# 0001.net
KiCad netlist of a schematic drawn in Altium Designer
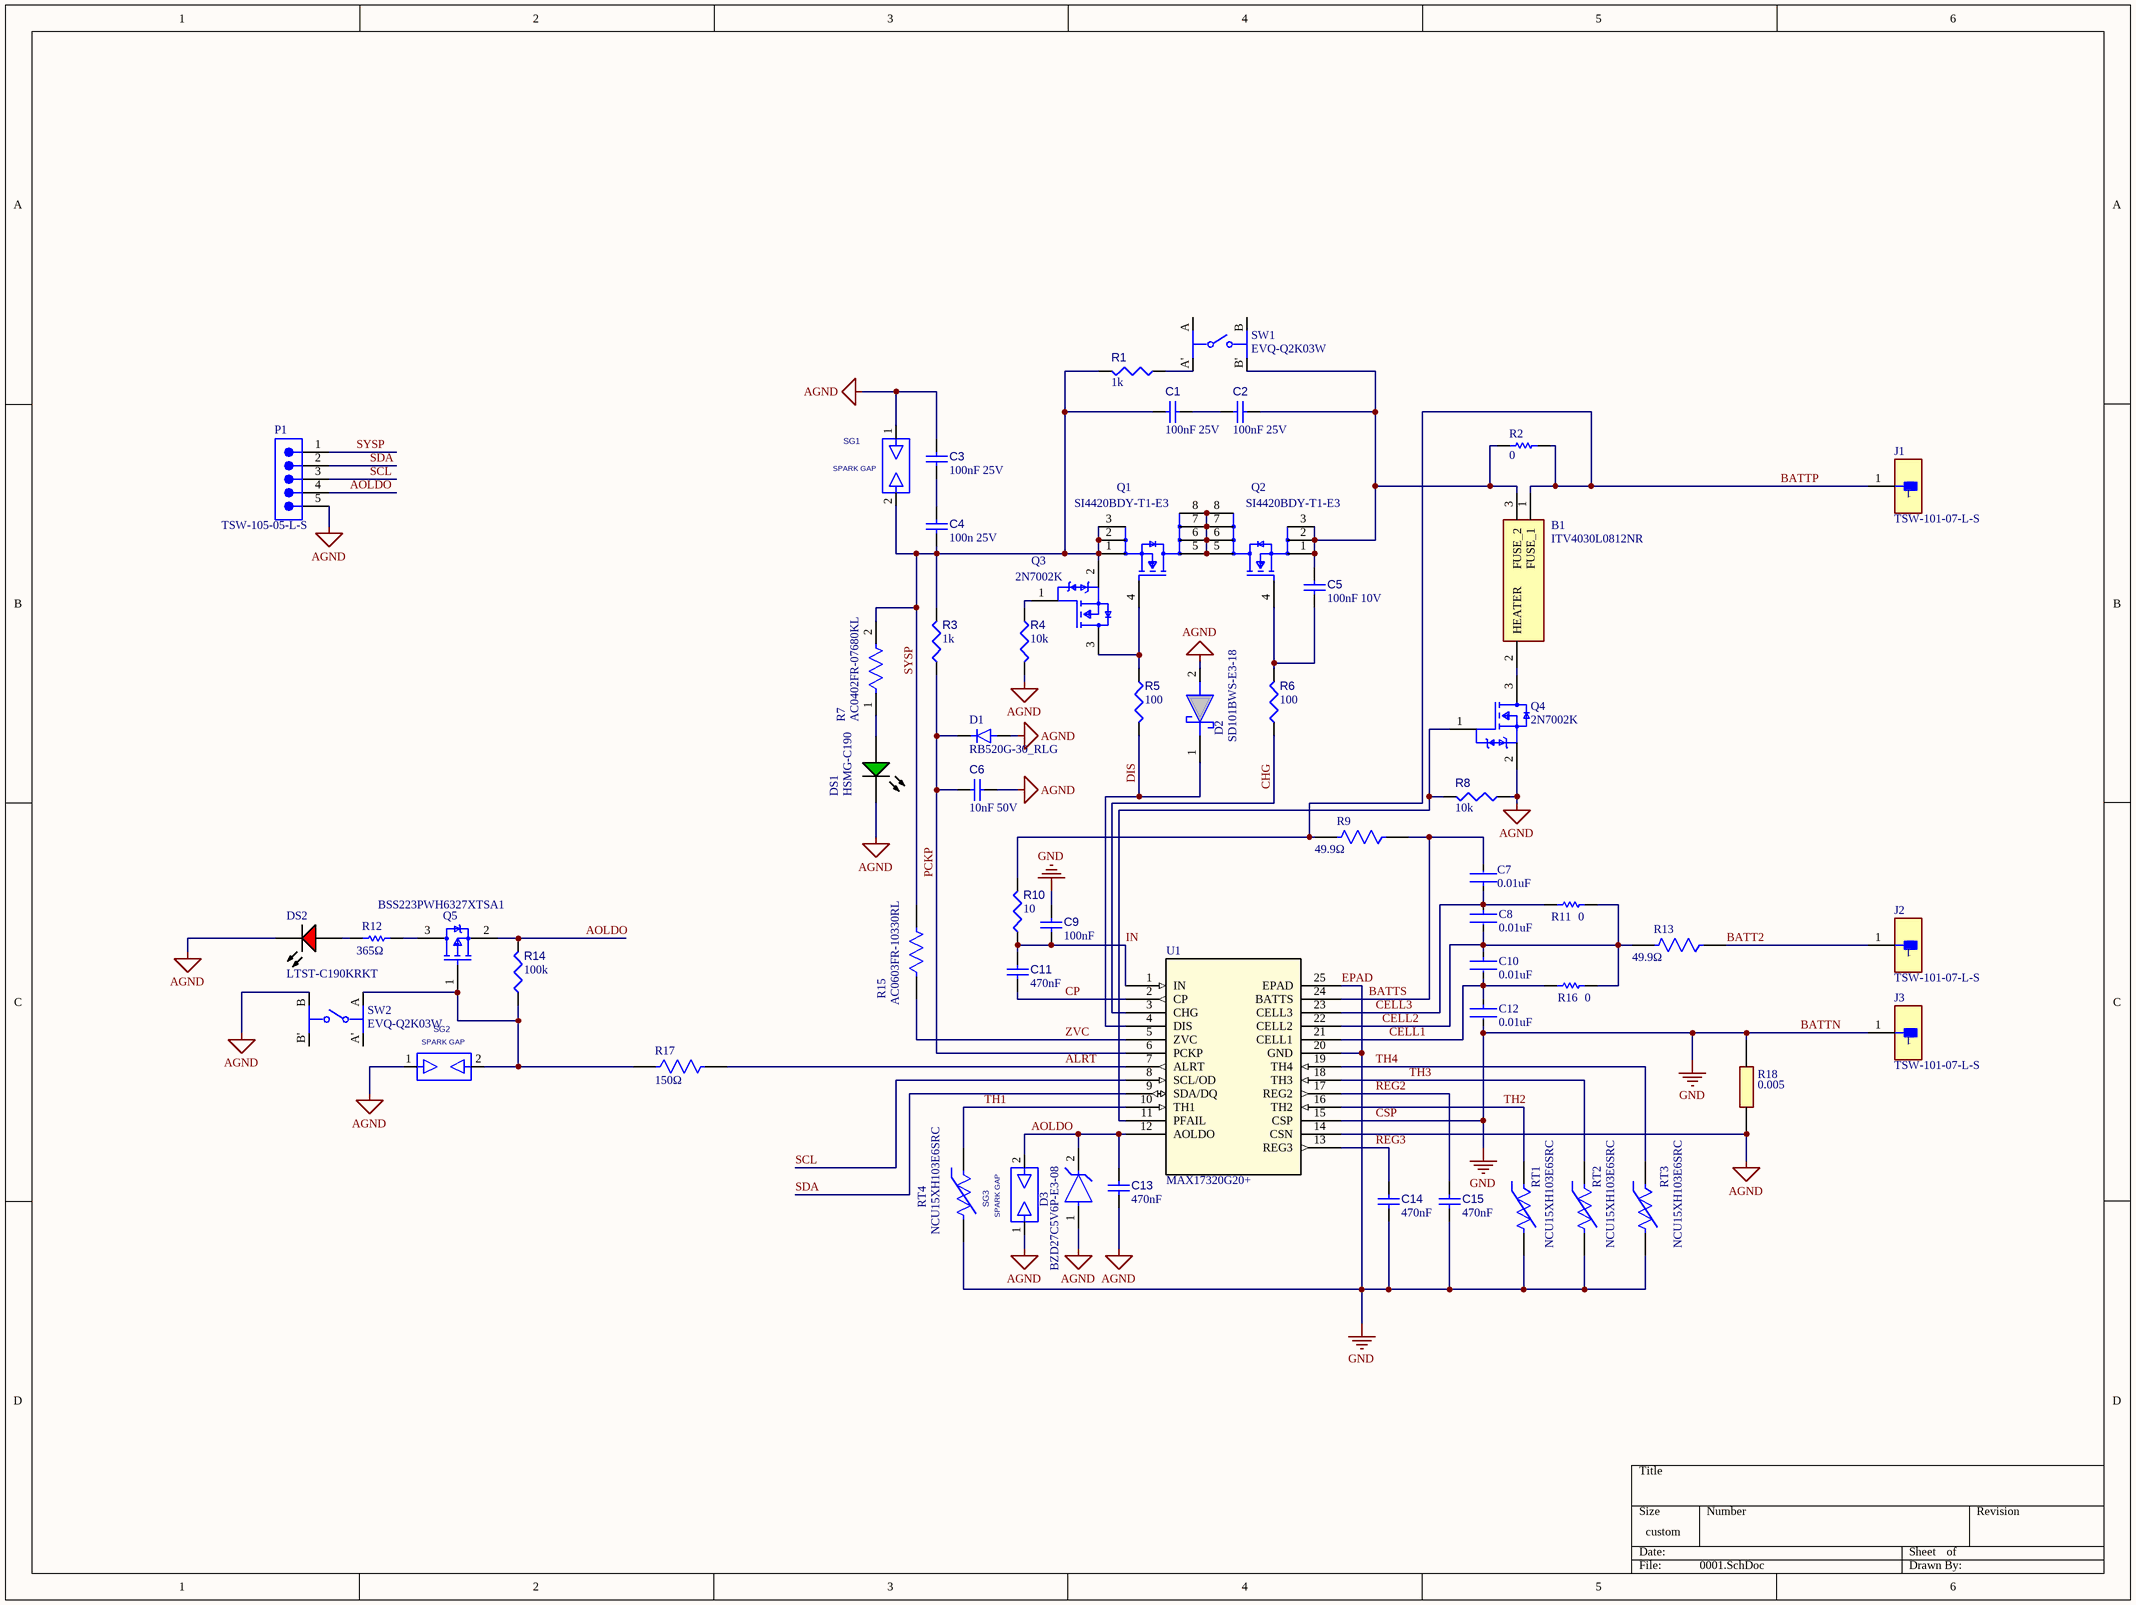
[diagram p0: 0001.SchDoc]

(export (version "E")
  (design (tool "Eeschema 10.0.6"))
  (components
    (comp (ref "B1")
      (value "ITV4030L0812NR")
      (footprint "ITV4030L0812NR")
      (description "Battery Management ITV 4.0*3.0MM 8V 12A")
      (fields (field (name "MOUSER PART NUMBER") "650-ITV4030L0812NR"))
      (libsource (lib "Pascal Doering") (part "ITV4030L0812NR"))
    )
    (comp (ref "C1")
      (value "100nF 25V")
      (footprint "CAPC0402(1005)60_L")
      (description "Chip Capacitor, 100nF +/-20%, 25V, 0402, Thickness 0.6 mm")
      (fields (field (name "TOLERANCE") "10%") (field (name "Comment") "Capacitor 100nF +/-20% 25V 0402"))
      (libsource (lib "Pascal Doering") (part "CAP-NP-2"))
    )
    (comp (ref "C2")
      (value "100nF 25V")
      (footprint "CAPC0402(1005)60_L")
      (description "Chip Capacitor, 100nF +/-20%, 25V, 0402, Thickness 0.6 mm")
      (fields (field (name "TOLERANCE") "10%") (field (name "Comment") "Capacitor 100nF +/-20% 25V 0402"))
      (libsource (lib "Pascal Doering") (part "CAP-NP-2"))
    )
    (comp (ref "C3")
      (value "100nF 25V")
      (footprint "CAPC0402(1005)60_L")
      (description "Chip Capacitor, 100nF +/-20%, 25V, 0402, Thickness 0.6 mm")
      (fields (field (name "TOLERANCE") "10%") (field (name "Comment") "Capacitor 100nF +/-20% 25V 0402"))
      (libsource (lib "Pascal Doering") (part "CAP-NP-2"))
    )
    (comp (ref "C4")
      (value "100n 25V")
      (footprint "CAPC0402(1005)60_L")
      (description "Chip Capacitor, 100nF +/-20%, 25V, 0402, Thickness 0.6 mm")
      (fields (field (name "TOLERANCE") "10%") (field (name "Comment") "Capacitor 100nF +/-20% 25V 0402"))
      (libsource (lib "Pascal Doering") (part "CAP-NP-2"))
    )
    (comp (ref "C5")
      (value "100nF 10V")
      (footprint "CAPC0402(1005)60_L")
      (description "Chip Capacitor, 100nF +/-20%, 10V, 0402, Thickness 0.6 mm")
      (fields (field (name "TOLERANCE") "20%") (field (name "Comment") "Capacitor 100nF +/-20% 10V 0402"))
      (libsource (lib "Pascal Doering") (part "CAP-NP-2"))
    )
    (comp (ref "C6")
      (value "10nF 50V")
      (footprint "CAPC0402(1005)60_L")
      (description "Chip Capacitor, 10nF +/-20%, 50V, 0402, Thickness 0.6 mm")
      (fields (field (name "TOLERANCE") "5%") (field (name "Comment") "Capacitor 10nF +/-20% 50V 0402"))
      (libsource (lib "Pascal Doering") (part "CAP-NP-2"))
    )
    (comp (ref "C7")
      (value "0.01uF")
      (footprint "FP-C1206C-EB-MFG")
      (description "C1206 10,000 pF X8R 20.00% 10 V")
      (fields
        (field (name "MANUFACTURER") "KEMET")
        (field (name "MANUFACTURER PART NUMBER") "C1206C103M8HACTU")
      )
      (libsource (lib "Altium Content Vault") (part "b4654b650e69147ec39a6b967a45e02"))
    )
    (comp (ref "C8")
      (value "0.01uF")
      (footprint "FP-C1206C-EB-MFG")
      (description "C1206 10,000 pF X8R 20.00% 10 V")
      (fields
        (field (name "MANUFACTURER") "KEMET")
        (field (name "MANUFACTURER PART NUMBER") "C1206C103M8HACTU")
      )
      (libsource (lib "Altium Content Vault") (part "b4654b650e69147ec39a6b967a45e02"))
    )
    (comp (ref "C9")
      (value "100nF")
      (footprint "CAPC0402(1005)60_L")
      (description "Chip Capacitor, 100nF +/-20%, 25V, 0402, Thickness 0.6 mm")
      (fields (field (name "TOLERANCE") "10%") (field (name "Comment") "Capacitor 100nF +/-20% 25V 0402"))
      (libsource (lib "Pascal Doering") (part "CAP-NP-2"))
    )
    (comp (ref "C10")
      (value "0.01uF")
      (footprint "FP-C1206C-EB-MFG")
      (description "C1206 10,000 pF X8R 20.00% 10 V")
      (fields
        (field (name "MANUFACTURER") "KEMET")
        (field (name "MANUFACTURER PART NUMBER") "C1206C103M8HACTU")
      )
      (libsource (lib "Altium Content Vault") (part "b4654b650e69147ec39a6b967a45e02"))
    )
    (comp (ref "C11")
      (value "470nF")
      (footprint "CAPC0603(1608)100_L")
      (description "Chip Capacitor, 470nF +/-20%, 25V, 0603, Thickness 1 mm")
      (fields (field (name "TOLERANCE") "10%") (field (name "Comment") "Capacitor 470nF +/-20% 25V 0603"))
      (libsource (lib "Pascal Doering") (part "CAP-NP-2"))
    )
    (comp (ref "C12")
      (value "0.01uF")
      (footprint "FP-C1206C-EB-MFG")
      (description "C1206 10,000 pF X8R 20.00% 10 V")
      (fields
        (field (name "MANUFACTURER") "KEMET")
        (field (name "MANUFACTURER PART NUMBER") "C1206C103M8HACTU")
      )
      (libsource (lib "Altium Content Vault") (part "b4654b650e69147ec39a6b967a45e02"))
    )
    (comp (ref "C13")
      (value "470nF")
      (footprint "CAPC0603(1608)100_L")
      (description "Chip Capacitor, 470nF +/-20%, 25V, 0603, Thickness 1 mm")
      (fields (field (name "TOLERANCE") "10%") (field (name "Comment") "Capacitor 470nF +/-20% 25V 0603"))
      (libsource (lib "Pascal Doering") (part "CAP-NP-2"))
    )
    (comp (ref "C14")
      (value "470nF")
      (footprint "CAPC0402(1005)60_L")
      (description "Chip Capacitor, 470nF +/-40%, 10V, 0402, Thickness 0.6 mm")
      (fields (field (name "TOLERANCE") "20%") (field (name "Comment") "Capacitor 470nF +/-40% 10V 0402"))
      (libsource (lib "Pascal Doering") (part "CAP-NP-2"))
    )
    (comp (ref "C15")
      (value "470nF")
      (footprint "CAPC0402(1005)60_L")
      (description "Chip Capacitor, 470nF +/-40%, 10V, 0402, Thickness 0.6 mm")
      (fields (field (name "TOLERANCE") "20%") (field (name "Comment") "Capacitor 470nF +/-40% 10V 0402"))
      (libsource (lib "Pascal Doering") (part "CAP-NP-2"))
    )
    (comp (ref "D1")
      (value "RB520G-30_RLG")
      (footprint "DIO_RB520G-30_RLG")
      (description "SOD-723F, 30V, 0.1A, Schottky Diode")
      (fields (field (name "MF") "Taiwan Semiconductor") (field (name "MP") "RB520G-30 RLG"))
      (libsource (lib "Pascal Doering") (part "RB520G-30_RLG"))
    )
    (comp (ref "D2")
      (value "SD101BWS-E3-18")
      (footprint "SOD2713X115N")
      (description "Schottky Diodes & Rectifiers 30mA 50Volt 2A IFSM")
      (fields (field (name "MOUSER PART NUMBER") "78-SD101BWS-E3-18"))
      (libsource (lib "Pascal Doering") (part "SD101BWS-E3-18"))
    )
    (comp (ref "D3")
      (value "BZD27C5V6P-E3-08")
      (footprint "FP-S8-V-3915_01-001-MFG")
      (description "DIODE ZENER 5.6V 800MW DO219AB")
      (fields
        (field (name "OCTOPART") "https://octopart.com/bzd27c5v6p-e3-08-vishay-30317385")
        (field (name "MANUFACTURER") "Vishay")
      )
      (libsource (lib "Altium Content Vault") (part "3fba79ac723ca0a4e69928609483429"))
    )
    (comp (ref "DS1")
      (value "HSMG-C190")
      (footprint "AVAG-HSMX-C190_V")
      (description "LED Uni-Color Green, 52 mW, 20 mA, -40 to 85 degC, 2-Pin SMD, RoHS, Tape and Reel")
      (fields (field (name "POWER") "52mW") (field (name "MANUFACTURER") "Avago"))
      (libsource (lib "Pascal Doering") (part "LED-GREEN-AK-2"))
    )
    (comp (ref "DS2")
      (value "LTST-C190KRKT")
      (footprint "LTST-C191KRKT_V")
      (description "LED Uni-Color Red, 62.5 mW, 25 mA, -30 to 85 degC, 2-Pin SMD, RoHS, Tape and Reel")
      (fields (field (name "POWER") "75mW") (field (name "MANUFACTURER") "Lite-On"))
      (libsource (lib "Pascal Doering") (part "LED-RED-AK-2"))
    )
    (comp (ref "J1")
      (value "TSW-101-07-L-S")
      (footprint "FP-TSW-101-07-L-S-MFG")
      (description "CONN HEADER VERT 1POS")
      (libsource (lib "Altium Content Vault") (part "dd45045ce8184df9e99e12baf3f412c"))
    )
    (comp (ref "J2")
      (value "TSW-101-07-L-S")
      (footprint "FP-TSW-101-07-L-S-MFG")
      (description "CONN HEADER VERT 1POS")
      (libsource (lib "Altium Content Vault") (part "dd45045ce8184df9e99e12baf3f412c"))
    )
    (comp (ref "J3")
      (value "TSW-101-07-L-S")
      (footprint "FP-TSW-101-07-L-S-MFG")
      (description "CONN HEADER VERT 1POS")
      (libsource (lib "Altium Content Vault") (part "dd45045ce8184df9e99e12baf3f412c"))
    )
    (comp (ref "P1")
      (value "TSW-105-05-L-S")
      (footprint "SMTC-TSW-105-05-X-S")
      (description "0.025\" SQ Post Header, Through-hole, Vertical, -55 to 125 degC, 2.54 mm Pitch, 5-Pin, Male, RoHS")
      (fields (field (name "MANUFACTURER") "Samtec"))
      (libsource (lib "Altium Content Vault") (part "SMTC-TSW-105-05-X-S"))
    )
    (comp (ref "Q1")
      (value "SI4420BDY-T1-E3")
      (footprint "FP-C-06527-MFG")
      (description "SI4420BDY-T1-E3 Si4420BDY Series 30 V 9.5 A 8.5 mOhm Surface Mount N-Channel Mosfet - SOIC-8")
      (libsource (lib "Altium Content Vault") (part "aae23f27f91e5e647325906a96994cf"))
    )
    (comp (ref "Q2")
      (value "SI4420BDY-T1-E3")
      (footprint "FP-C-06527-MFG")
      (description "SI4420BDY-T1-E3 Si4420BDY Series 30 V 9.5 A 8.5 mOhm Surface Mount N-Channel Mosfet - SOIC-8")
      (libsource (lib "Altium Content Vault") (part "aae23f27f91e5e647325906a96994cf"))
    )
    (comp (ref "Q3")
      (value "2N7002K")
      (footprint "FP-318-08-MFG")
      (description "MOSFET N-CH 60V 300MA SOT23")
      (fields
        (field (name "OCTOPART") "https://octopart.com/2n7002k-on+semiconductor-84408900")
        (field (name "MANUFACTURER") "ON Semiconductor")
      )
      (libsource (lib "Altium Content Vault") (part "40bafa8609a25cdbb0dab398ef4a0d9"))
    )
    (comp (ref "Q4")
      (value "2N7002K")
      (footprint "FP-318-08-MFG")
      (description "MOSFET N-CH 60V 300MA SOT23")
      (fields
        (field (name "OCTOPART") "https://octopart.com/2n7002k-on+semiconductor-84408900")
        (field (name "MANUFACTURER") "ON Semiconductor")
      )
      (libsource (lib "Altium Content Vault") (part "40bafa8609a25cdbb0dab398ef4a0d9"))
    )
    (comp (ref "Q5")
      (value "BSS223PWH6327XTSA1")
      (footprint "FP-PG-SOT323-3-MFG")
      (description "MOSFET P-CH 20V 390MA SOT-323")
      (libsource (lib "Altium Content Vault") (part "bfa2fa1666557a2a9b55830ca27aed5"))
    )
    (comp (ref "R1")
      (value "1k")
      (footprint "RESC0402(1005)_L")
      (description "Chip Resistor, 1 kOhms, +/-5 %, 63 mW, -55 to 155 degC, 0402")
      (fields (field (name "TOLERANCE") "5%") (field (name "POWER") "63mW"))
      (libsource (lib "Pascal Doering") (part "RES-2"))
    )
    (comp (ref "R2")
      (value "0")
      (footprint "RESC2013X60X35ML10T20")
      (description "Chip Resistor, 0 Ohm, 0.125 W, -55 to 155 degC, 0805 (2012 Metric)")
      (fields (field (name "POWER") "125mW") (field (name "TOLERANCE") "5%"))
      (libsource (lib "") (part "RES-2_1"))
    )
    (comp (ref "R3")
      (value "1k")
      (footprint "RESC0402(1005)_L")
      (description "Chip Resistor, 1 kOhms, +/-5 %, 63 mW, -55 to 155 degC, 0402")
      (fields (field (name "TOLERANCE") "5%") (field (name "POWER") "63mW"))
      (libsource (lib "Pascal Doering") (part "RES-2"))
    )
    (comp (ref "R4")
      (value "10k")
      (footprint "RESC0402(1005)_L")
      (description "Chip Resistor, 10 kOhms, +/-1 %, 63 mW, -55 to 125 degC, 0402")
      (fields (field (name "POWER") "63mW") (field (name "TOLERANCE") "1%"))
      (libsource (lib "Pascal Doering") (part "RES-2"))
    )
    (comp (ref "R5")
      (value "100")
      (footprint "RESC0402(1005)_L")
      (description "Chip Resistor, 100 Ohms, +/-1 %, 63 mW, -55 to 155 degC, 0402")
      (fields (field (name "POWER") "63mW") (field (name "TOLERANCE") "1%"))
      (libsource (lib "Pascal Doering") (part "RES-2"))
    )
    (comp (ref "R6")
      (value "100")
      (footprint "RESC0402(1005)_L")
      (description "Chip Resistor, 100 Ohms, +/-1 %, 63 mW, -55 to 155 degC, 0402")
      (fields (field (name "POWER") "63mW") (field (name "TOLERANCE") "1%"))
      (libsource (lib "Pascal Doering") (part "RES-2"))
    )
    (comp (ref "R7")
      (value "AC0402FR-07680KL")
      (footprint "FP-AC0402-IPC_C")
      (description "RES 680kΩ ±1% 0.063W 0402")
      (fields (field (name "TOLERANCE") "1%"))
      (libsource (lib "") (part "1029c3af85768c4190bb7ad29bc67b5_1"))
    )
    (comp (ref "R8")
      (value "10k")
      (footprint "RESC0402(1005)_L")
      (description "Chip Resistor, 10 kOhms, +/-1 %, 63 mW, -55 to 125 degC, 0402")
      (fields (field (name "POWER") "63mW") (field (name "TOLERANCE") "1%"))
      (libsource (lib "Pascal Doering") (part "RES-2"))
    )
    (comp (ref "R9")
      (value "49.9Ω")
      (footprint "FP-RMCF0805-IPC_C")
      (description "49.9Ω ±1% 0.125W 0805 Thick Film Chip Resistor AEC-Q200 compliant")
      (fields (field (name "TOLERANCE") "1%"))
      (libsource (lib "Altium Content Vault") (part "1029c3af85768c4190bb7ad29bc67b5"))
    )
    (comp (ref "R10")
      (value "10")
      (footprint "RESC0402(1005)_L")
      (description "Chip Resistor, 10 Ohms, +/-1 %, 63 mW, -55 to 155 degC, 0402")
      (fields (field (name "TOLERANCE") "1%") (field (name "POWER") "63mW"))
      (libsource (lib "Pascal Doering") (part "RES-2"))
    )
    (comp (ref "R11")
      (value "0")
      (footprint "RESC1005X40X25ML05T10")
      (description "Chip Resistor, 0 Ohm, 0.063 W, -55 to 155 degC, 0402 (1005 Metric)")
      (fields (field (name "POWER") "63mW") (field (name "Comment") "Resistor 0R 0402 63 mW"))
      (libsource (lib "") (part "RES-2_1"))
    )
    (comp (ref "R12")
      (value "365Ω")
      (footprint "RESC1005X40X25NL05T10")
      (fields (field (name "MANUFACTURER") "Yageo") (field (name "PART NUMBER") "RC0402FR-07365RL"))
      (libsource (lib "Altium Content Vault") (part "RES"))
    )
    (comp (ref "R13")
      (value "49.9Ω")
      (footprint "FP-RMCF0805-IPC_C")
      (description "49.9Ω ±1% 0.125W 0805 Thick Film Chip Resistor AEC-Q200 compliant")
      (fields (field (name "TOLERANCE") "1%"))
      (libsource (lib "Altium Content Vault") (part "1029c3af85768c4190bb7ad29bc67b5"))
    )
    (comp (ref "R14")
      (value "100k")
      (footprint "RESC0402(1005)_L")
      (description "Chip Resistor, 100 kOhms, +/-1 %, 63 mW, -55 to 155 degC, 0402")
      (fields (field (name "TOLERANCE") "1%") (field (name "POWER") "63mW"))
      (libsource (lib "Pascal Doering") (part "RES-2"))
    )
    (comp (ref "R15")
      (value "AC0603FR-10330RL")
      (footprint "FP-AC0603-IPC_A")
      (description "RES 330Ω 1.00% 0.1W 0603")
      (libsource (lib "Altium Content Vault") (part "1029c3af85768c4190bb7ad29bc67b5"))
    )
    (comp (ref "R16")
      (value "0")
      (footprint "RESC1005X40X25ML05T10")
      (description "Chip Resistor, 0 Ohm, 0.063 W, -55 to 155 degC, 0402 (1005 Metric)")
      (fields (field (name "POWER") "63mW") (field (name "Comment") "Resistor 0R 0402 63 mW"))
      (libsource (lib "") (part "RES-2_1"))
    )
    (comp (ref "R17")
      (value "150Ω")
      (footprint "FP-AF0402-IPC_B")
      (description "Anti-Sulfurated Chip Resistors Automotive Grade 150Ω 5% 100ppm/°C 0402")
      (fields (field (name "TOLERANCE") "5%"))
      (libsource (lib "Altium Content Vault") (part "1029c3af85768c4190bb7ad29bc67b5"))
    )
    (comp (ref "R18")
      (value "0.005")
      (footprint "RESC1608X80N")
      (description "TT ELECTRONICS / WELWYN - MFC0603-R005FT5 - CURRENT SENSE RES, 0R005, 1%, 500 MW")
      (fields
        (field (name "MOUSER PART NUMBER") "756-MFC0603-R005FT5")
        (field (name "MANUFACTURER_PART_NUMBER") "MFC0603-R005FT5")
      )
      (libsource (lib "Pascal Doering") (part "MFC0603-R005FT5"))
    )
    (comp (ref "RT1")
      (value "NCU15XH103E6SRC")
      (footprint "FP-NCP15-NCU15-0_05-IPC_A")
      (description "NTC Thermistor for Temperature Sensor, Automotive, 0402, 10kΩ, 3%, 0.1mA, 5V")
      (libsource (lib "Altium Content Vault") (part "3b148a6ebabc5fb4d708a66c052d352"))
    )
    (comp (ref "RT2")
      (value "NCU15XH103E6SRC")
      (footprint "FP-NCP15-NCU15-0_05-IPC_A")
      (description "NTC Thermistor for Temperature Sensor, Automotive, 0402, 10kΩ, 3%, 0.1mA, 5V")
      (libsource (lib "Altium Content Vault") (part "3b148a6ebabc5fb4d708a66c052d352"))
    )
    (comp (ref "RT3")
      (value "NCU15XH103E6SRC")
      (footprint "FP-NCP15-NCU15-0_05-IPC_A")
      (description "NTC Thermistor for Temperature Sensor, Automotive, 0402, 10kΩ, 3%, 0.1mA, 5V")
      (libsource (lib "Altium Content Vault") (part "3b148a6ebabc5fb4d708a66c052d352"))
    )
    (comp (ref "RT4")
      (value "NCU15XH103E6SRC")
      (footprint "FP-NCP15-NCU15-0_05-IPC_A")
      (description "NTC Thermistor for Temperature Sensor, Automotive, 0402, 10kΩ, 3%, 0.1mA, 5V")
      (libsource (lib "Altium Content Vault") (part "3b148a6ebabc5fb4d708a66c052d352"))
    )
    (comp (ref "SG1")
      (value "SPARK GAP")
      (footprint "EVKIT_SPARK_GAP")
      (description "EVKIT SPARK GAP")
      (libsource (lib "*") (part "EK_SPARKGAP"))
    )
    (comp (ref "SG2")
      (value "SPARK GAP")
      (footprint "EVKIT_SPARK_GAP")
      (description "EVKIT SPARK GAP")
      (libsource (lib "*") (part "EK_SPARKGAP"))
    )
    (comp (ref "SG3")
      (value "SPARK GAP")
      (footprint "EVKIT_SPARK_GAP")
      (description "EVKIT SPARK GAP")
      (libsource (lib "*") (part "EK_SPARKGAP"))
    )
    (comp (ref "SW1")
      (value "EVQ-Q2K03W")
      (footprint "FP-EVQ-Q2K03W-MFG")
      (description "SWITCH TACTILE SPST-NO 0.02A 15V")
      (fields
        (field (name "MANUFACTURER") "Panasonic Electronic Components")
        (field (name "OCTOPART") "https://octopart.com/evq-q2k03w-panasonic-1224370")
      )
      (libsource (lib "Altium Content Vault") (part "9677229990528492022b31d4503349f"))
    )
    (comp (ref "SW2")
      (value "EVQ-Q2K03W")
      (footprint "FP-EVQ-Q2K03W-MFG")
      (description "SWITCH TACTILE SPST-NO 0.02A 15V")
      (fields
        (field (name "MANUFACTURER") "Panasonic Electronic Components")
        (field (name "OCTOPART") "https://octopart.com/evq-q2k03w-panasonic-1224370")
      )
      (libsource (lib "Altium Content Vault") (part "9677229990528492022b31d4503349f"))
    )
    (comp (ref "U1")
      (value "MAX17320G20+")
      (footprint "21-0139I_T2444-4_MXM")
      (fields (field (name "COPYRIGHT") "Copyright (C) 2025 Ultra Librarian. All rights reserved."))
      (libsource (lib "Pascal Doering") (part "MAX17320G20+"))
    )
  )
  (nets
    (net (code "1") (name "/ALRT") (class "Default")
      (node (ref "R17") (pin "2") (pinfunction "2_2") (pintype "passive"))
      (node (ref "U1") (pin "7") (pinfunction "ALRT_7") (pintype "output"))
    )
    (net (code "2") (name "/AOLDO") (class "Default")
      (node (ref "C13") (pin "1") (pinfunction "1_1") (pintype "passive"))
      (node (ref "D3") (pin "2") (pinfunction "C_2") (pintype "passive"))
      (node (ref "P1") (pin "4") (pinfunction "4_4") (pintype "passive"))
      (node (ref "Q5") (pin "2") (pinfunction "Source_2") (pintype "passive"))
      (node (ref "R14") (pin "2") (pinfunction "2_2") (pintype "passive"))
      (node (ref "SG3") (pin "2") (pinfunction "2_2") (pintype "bidirectional"))
      (node (ref "U1") (pin "12") (pinfunction "AOLDO_12") (pintype "passive"))
    )
    (net (code "3") (name "/BATT2") (class "Default")
      (node (ref "J2") (pin "1") (pinfunction "1_1") (pintype "passive"))
      (node (ref "R13") (pin "1") (pinfunction "1_1") (pintype "passive"))
    )
    (net (code "4") (name "/BATTP") (class "Default")
      (node (ref "B1") (pin "1") (pinfunction "FUSE_1_1") (pintype "passive"))
      (node (ref "J1") (pin "1") (pinfunction "1_1") (pintype "passive"))
      (node (ref "R10") (pin "2") (pinfunction "2_2") (pintype "passive"))
      (node (ref "R2") (pin "2") (pinfunction "2_2") (pintype "passive"))
      (node (ref "R9") (pin "2") (pinfunction "2_2") (pintype "passive"))
    )
    (net (code "5") (name "/BATTS") (class "Default")
      (node (ref "C7") (pin "2") (pinfunction "2_2") (pintype "passive"))
      (node (ref "R9") (pin "1") (pinfunction "1_1") (pintype "passive"))
      (node (ref "U1") (pin "24") (pinfunction "BATTS_24") (pintype "passive"))
    )
    (net (code "6") (name "/CELL1") (class "Default")
      (node (ref "C10") (pin "2") (pinfunction "2_2") (pintype "passive"))
      (node (ref "C12") (pin "1") (pinfunction "1_1") (pintype "passive"))
      (node (ref "R16") (pin "1") (pinfunction "1_1") (pintype "passive"))
      (node (ref "U1") (pin "21") (pinfunction "CELL1_21") (pintype "passive"))
    )
    (net (code "7") (name "/CELL2") (class "Default")
      (node (ref "C10") (pin "1") (pinfunction "1_1") (pintype "passive"))
      (node (ref "C8") (pin "2") (pinfunction "2_2") (pintype "passive"))
      (node (ref "R11") (pin "2") (pinfunction "2_2") (pintype "passive"))
      (node (ref "R13") (pin "2") (pinfunction "2_2") (pintype "passive"))
      (node (ref "R16") (pin "2") (pinfunction "2_2") (pintype "passive"))
      (node (ref "U1") (pin "22") (pinfunction "CELL2_22") (pintype "passive"))
    )
    (net (code "8") (name "/CELL3") (class "Default")
      (node (ref "C7") (pin "1") (pinfunction "1_1") (pintype "passive"))
      (node (ref "C8") (pin "1") (pinfunction "1_1") (pintype "passive"))
      (node (ref "R11") (pin "1") (pinfunction "1_1") (pintype "passive"))
      (node (ref "U1") (pin "23") (pinfunction "CELL3_23") (pintype "passive"))
    )
    (net (code "9") (name "/CHG") (class "Default")
      (node (ref "R6") (pin "2") (pinfunction "2_2") (pintype "passive"))
      (node (ref "U1") (pin "3") (pinfunction "CHG_3") (pintype "passive"))
    )
    (net (code "10") (name "/CP") (class "Default")
      (node (ref "C11") (pin "2") (pinfunction "2_2") (pintype "passive"))
      (node (ref "U1") (pin "2") (pinfunction "CP_2") (pintype "output"))
    )
    (net (code "11") (name "/DIS") (class "Default")
      (node (ref "D2") (pin "1") (pinfunction "K_1") (pintype "passive"))
      (node (ref "R5") (pin "1") (pinfunction "1_1") (pintype "passive"))
      (node (ref "U1") (pin "4") (pinfunction "DIS_4") (pintype "passive"))
    )
    (net (code "12") (name "/IN") (class "Default")
      (node (ref "C11") (pin "1") (pinfunction "1_1") (pintype "passive"))
      (node (ref "C9") (pin "1") (pinfunction "1_1") (pintype "passive"))
      (node (ref "R10") (pin "1") (pinfunction "1_1") (pintype "passive"))
      (node (ref "U1") (pin "1") (pinfunction "IN_1") (pintype "input"))
    )
    (net (code "13") (name "/PCKP") (class "Default")
      (node (ref "C6") (pin "2") (pinfunction "2_2") (pintype "passive"))
      (node (ref "D1") (pin "C") (pinfunction "K_C") (pintype "passive"))
      (node (ref "R3") (pin "2") (pinfunction "2_2") (pintype "passive"))
      (node (ref "U1") (pin "6") (pinfunction "PCKP_6") (pintype "passive"))
    )
    (net (code "14") (name "/REG2") (class "Default")
      (node (ref "C15") (pin "1") (pinfunction "1_1") (pintype "passive"))
      (node (ref "U1") (pin "17") (pinfunction "REG2_17") (pintype "output"))
    )
    (net (code "15") (name "/REG3") (class "Default")
      (node (ref "C14") (pin "1") (pinfunction "1_1") (pintype "passive"))
      (node (ref "U1") (pin "13") (pinfunction "REG3_13") (pintype "output"))
    )
    (net (code "16") (name "/SCL") (class "Default")
      (node (ref "P1") (pin "3") (pinfunction "3_3") (pintype "passive"))
      (node (ref "U1") (pin "8") (pinfunction "SCL/OD_8") (pintype "input"))
    )
    (net (code "17") (name "/SDA") (class "Default")
      (node (ref "P1") (pin "2") (pinfunction "2_2") (pintype "passive"))
      (node (ref "U1") (pin "9") (pinfunction "SDA/DQ_9") (pintype "bidirectional"))
    )
    (net (code "18") (name "/SYSP") (class "Default")
      (node (ref "C1") (pin "1") (pinfunction "1_1") (pintype "passive"))
      (node (ref "C4") (pin "2") (pinfunction "2_2") (pintype "passive"))
      (node (ref "P1") (pin "1") (pinfunction "1_1") (pintype "passive"))
      (node (ref "Q1") (pin "1") (pinfunction "S_1") (pintype "passive"))
      (node (ref "Q1") (pin "2") (pinfunction "S_2") (pintype "passive"))
      (node (ref "Q1") (pin "3") (pinfunction "S_3") (pintype "passive"))
      (node (ref "Q3") (pin "2") (pinfunction "Source_2") (pintype "passive"))
      (node (ref "R1") (pin "2") (pinfunction "2_2") (pintype "passive"))
      (node (ref "R15") (pin "2") (pinfunction "2_2") (pintype "passive"))
      (node (ref "R3") (pin "1") (pinfunction "1_1") (pintype "passive"))
      (node (ref "R7") (pin "2") (pinfunction "2_2") (pintype "passive"))
      (node (ref "SG1") (pin "2") (pinfunction "2_2") (pintype "bidirectional"))
    )
    (net (code "19") (name "/TH1") (class "Default")
      (node (ref "RT4") (pin "1") (pinfunction "1_1") (pintype "passive"))
      (node (ref "U1") (pin "10") (pinfunction "TH1_10") (pintype "input"))
    )
    (net (code "20") (name "/TH2") (class "Default")
      (node (ref "RT1") (pin "1") (pinfunction "1_1") (pintype "passive"))
      (node (ref "U1") (pin "16") (pinfunction "TH2_16") (pintype "input"))
    )
    (net (code "21") (name "/TH3") (class "Default")
      (node (ref "RT2") (pin "1") (pinfunction "1_1") (pintype "passive"))
      (node (ref "U1") (pin "18") (pinfunction "TH3_18") (pintype "input"))
    )
    (net (code "22") (name "/TH4") (class "Default")
      (node (ref "RT3") (pin "1") (pinfunction "1_1") (pintype "passive"))
      (node (ref "U1") (pin "19") (pinfunction "TH4_19") (pintype "input"))
    )
    (net (code "23") (name "/ZVC") (class "Default")
      (node (ref "R15") (pin "1") (pinfunction "1_1") (pintype "passive"))
      (node (ref "U1") (pin "5") (pinfunction "ZVC_5") (pintype "passive"))
    )
    (net (code "24") (name "AGND") (class "Default")
      (node (ref "C13") (pin "2") (pinfunction "2_2") (pintype "passive"))
      (node (ref "C3") (pin "1") (pinfunction "1_1") (pintype "passive"))
      (node (ref "C6") (pin "1") (pinfunction "1_1") (pintype "passive"))
      (node (ref "D1") (pin "A") (pinfunction "A_A") (pintype "passive"))
      (node (ref "D2") (pin "2") (pinfunction "A_2") (pintype "passive"))
      (node (ref "D3") (pin "1") (pinfunction "A_1") (pintype "passive"))
      (node (ref "DS1") (pin "2") (pinfunction "K_2") (pintype "passive"))
      (node (ref "DS2") (pin "2") (pinfunction "K_2") (pintype "passive"))
      (node (ref "P1") (pin "5") (pinfunction "5_5") (pintype "passive"))
      (node (ref "Q4") (pin "2") (pinfunction "Source_2") (pintype "passive"))
      (node (ref "R18") (pin "1") (pinfunction "1_1") (pintype "passive"))
      (node (ref "R4") (pin "1") (pinfunction "1_1") (pintype "passive"))
      (node (ref "R8") (pin "1") (pinfunction "1_1") (pintype "passive"))
      (node (ref "SG1") (pin "1") (pinfunction "1_1") (pintype "bidirectional"))
      (node (ref "SG2") (pin "1") (pinfunction "1_1") (pintype "bidirectional"))
      (node (ref "SG3") (pin "1") (pinfunction "1_1") (pintype "bidirectional"))
      (node (ref "SW2") (pin "B") (pinfunction "B_B") (pintype "passive"))
      (node (ref "U1") (pin "14") (pinfunction "CSN_14") (pintype "passive"))
    )
    (net (code "25") (name "GND") (class "Default")
      (node (ref "C12") (pin "2") (pinfunction "2_2") (pintype "passive"))
      (node (ref "C14") (pin "2") (pinfunction "2_2") (pintype "passive"))
      (node (ref "C15") (pin "2") (pinfunction "2_2") (pintype "passive"))
      (node (ref "C9") (pin "2") (pinfunction "2_2") (pintype "passive"))
      (node (ref "J3") (pin "1") (pinfunction "1_1") (pintype "passive"))
      (node (ref "R18") (pin "2") (pinfunction "2_2") (pintype "passive"))
      (node (ref "RT1") (pin "2") (pinfunction "2_2") (pintype "passive"))
      (node (ref "RT2") (pin "2") (pinfunction "2_2") (pintype "passive"))
      (node (ref "RT3") (pin "2") (pinfunction "2_2") (pintype "passive"))
      (node (ref "RT4") (pin "2") (pinfunction "2_2") (pintype "passive"))
      (node (ref "U1") (pin "15") (pinfunction "CSP_15") (pintype "passive"))
      (node (ref "U1") (pin "20") (pinfunction "GND_20") (pintype "power_in"))
      (node (ref "U1") (pin "25") (pinfunction "EPAD_25") (pintype "power_in"))
    )
    (net (code "26") (name "Net-(B1-FUSE_2)") (class "Default")
      (node (ref "B1") (pin "3") (pinfunction "FUSE_2_3") (pintype "passive"))
      (node (ref "C2") (pin "2") (pinfunction "2_2") (pintype "passive"))
      (node (ref "C5") (pin "2") (pinfunction "2_2") (pintype "passive"))
      (node (ref "Q2") (pin "1") (pinfunction "S_1") (pintype "passive"))
      (node (ref "Q2") (pin "2") (pinfunction "S_2") (pintype "passive"))
      (node (ref "Q2") (pin "3") (pinfunction "S_3") (pintype "passive"))
      (node (ref "R2") (pin "1") (pinfunction "1_1") (pintype "passive"))
      (node (ref "SW1") (pin "B'") (pinfunction "B'_B'") (pintype "passive"))
    )
    (net (code "27") (name "Net-(B1-HEATER)") (class "Default")
      (node (ref "B1") (pin "2") (pinfunction "HEATER_2") (pintype "passive"))
      (node (ref "Q4") (pin "3") (pinfunction "Drain_3") (pintype "passive"))
    )
    (net (code "28") (name "Net-(C1-Pad2)") (class "Default")
      (node (ref "C1") (pin "2") (pinfunction "2_2") (pintype "passive"))
      (node (ref "C2") (pin "1") (pinfunction "1_1") (pintype "passive"))
    )
    (net (code "29") (name "Net-(C3-Pad2)") (class "Default")
      (node (ref "C3") (pin "2") (pinfunction "2_2") (pintype "passive"))
      (node (ref "C4") (pin "1") (pinfunction "1_1") (pintype "passive"))
    )
    (net (code "30") (name "Net-(DS1-A)") (class "Default")
      (node (ref "DS1") (pin "1") (pinfunction "A_1") (pintype "passive"))
      (node (ref "R7") (pin "1") (pinfunction "1_1") (pintype "passive"))
    )
    (net (code "31") (name "Net-(DS2-A)") (class "Default")
      (node (ref "DS2") (pin "1") (pinfunction "A_1") (pintype "passive"))
      (node (ref "R12") (pin "1") (pinfunction "1_1") (pintype "passive"))
    )
    (net (code "32") (name "Net-(Q1-D-Pad5)") (class "Default")
      (node (ref "Q1") (pin "5") (pinfunction "D_5") (pintype "passive"))
      (node (ref "Q1") (pin "6") (pinfunction "D_6") (pintype "passive"))
      (node (ref "Q1") (pin "7") (pinfunction "D_7") (pintype "passive"))
      (node (ref "Q1") (pin "8") (pinfunction "D_8") (pintype "passive"))
      (node (ref "Q2") (pin "5") (pinfunction "D_5") (pintype "passive"))
      (node (ref "Q2") (pin "6") (pinfunction "D_6") (pintype "passive"))
      (node (ref "Q2") (pin "7") (pinfunction "D_7") (pintype "passive"))
      (node (ref "Q2") (pin "8") (pinfunction "D_8") (pintype "passive"))
    )
    (net (code "33") (name "Net-(Q1-G)") (class "Default")
      (node (ref "Q1") (pin "4") (pinfunction "G_4") (pintype "passive"))
      (node (ref "Q3") (pin "3") (pinfunction "Drain_3") (pintype "passive"))
      (node (ref "R5") (pin "2") (pinfunction "2_2") (pintype "passive"))
    )
    (net (code "34") (name "Net-(Q2-G)") (class "Default")
      (node (ref "C5") (pin "1") (pinfunction "1_1") (pintype "passive"))
      (node (ref "Q2") (pin "4") (pinfunction "G_4") (pintype "passive"))
      (node (ref "R6") (pin "1") (pinfunction "1_1") (pintype "passive"))
    )
    (net (code "35") (name "Net-(Q3-Gate)") (class "Default")
      (node (ref "Q3") (pin "1") (pinfunction "Gate_1") (pintype "passive"))
      (node (ref "R4") (pin "2") (pinfunction "2_2") (pintype "passive"))
    )
    (net (code "36") (name "Net-(Q4-Gate)") (class "Default")
      (node (ref "Q4") (pin "1") (pinfunction "Gate_1") (pintype "passive"))
      (node (ref "R8") (pin "2") (pinfunction "2_2") (pintype "passive"))
      (node (ref "U1") (pin "11") (pinfunction "PFAIL_11") (pintype "passive"))
    )
    (net (code "37") (name "Net-(Q5-Drain)") (class "Default")
      (node (ref "Q5") (pin "3") (pinfunction "Drain_3") (pintype "passive"))
      (node (ref "R12") (pin "2") (pinfunction "2_2") (pintype "passive"))
    )
    (net (code "38") (name "Net-(Q5-Gate)") (class "Default")
      (node (ref "Q5") (pin "1") (pinfunction "Gate_1") (pintype "passive"))
      (node (ref "R14") (pin "1") (pinfunction "1_1") (pintype "passive"))
      (node (ref "R17") (pin "1") (pinfunction "1_1") (pintype "passive"))
      (node (ref "SG2") (pin "2") (pinfunction "2_2") (pintype "bidirectional"))
      (node (ref "SW2") (pin "A") (pinfunction "A_A") (pintype "passive"))
    )
    (net (code "39") (name "Net-(R1-Pad1)") (class "Default")
      (node (ref "R1") (pin "1") (pinfunction "1_1") (pintype "passive"))
      (node (ref "SW1") (pin "A'") (pinfunction "A'_A'") (pintype "passive"))
    )
    (net (code "40") (name "unconnected-(SW1-PadA)") (class "Default")
      (node (ref "SW1") (pin "A") (pinfunction "A_A") (pintype "passive"))
    )
    (net (code "41") (name "unconnected-(SW1-PadB)") (class "Default")
      (node (ref "SW1") (pin "B") (pinfunction "B_B") (pintype "passive"))
    )
    (net (code "42") (name "unconnected-(SW2-PadA')") (class "Default")
      (node (ref "SW2") (pin "A'") (pinfunction "A'_A'") (pintype "passive"))
    )
    (net (code "43") (name "unconnected-(SW2-PadB')") (class "Default")
      (node (ref "SW2") (pin "B'") (pinfunction "B'_B'") (pintype "passive"))
    )
  )
)
